# USB-C.net
KiCad netlist of a schematic drawn in Altium Designer
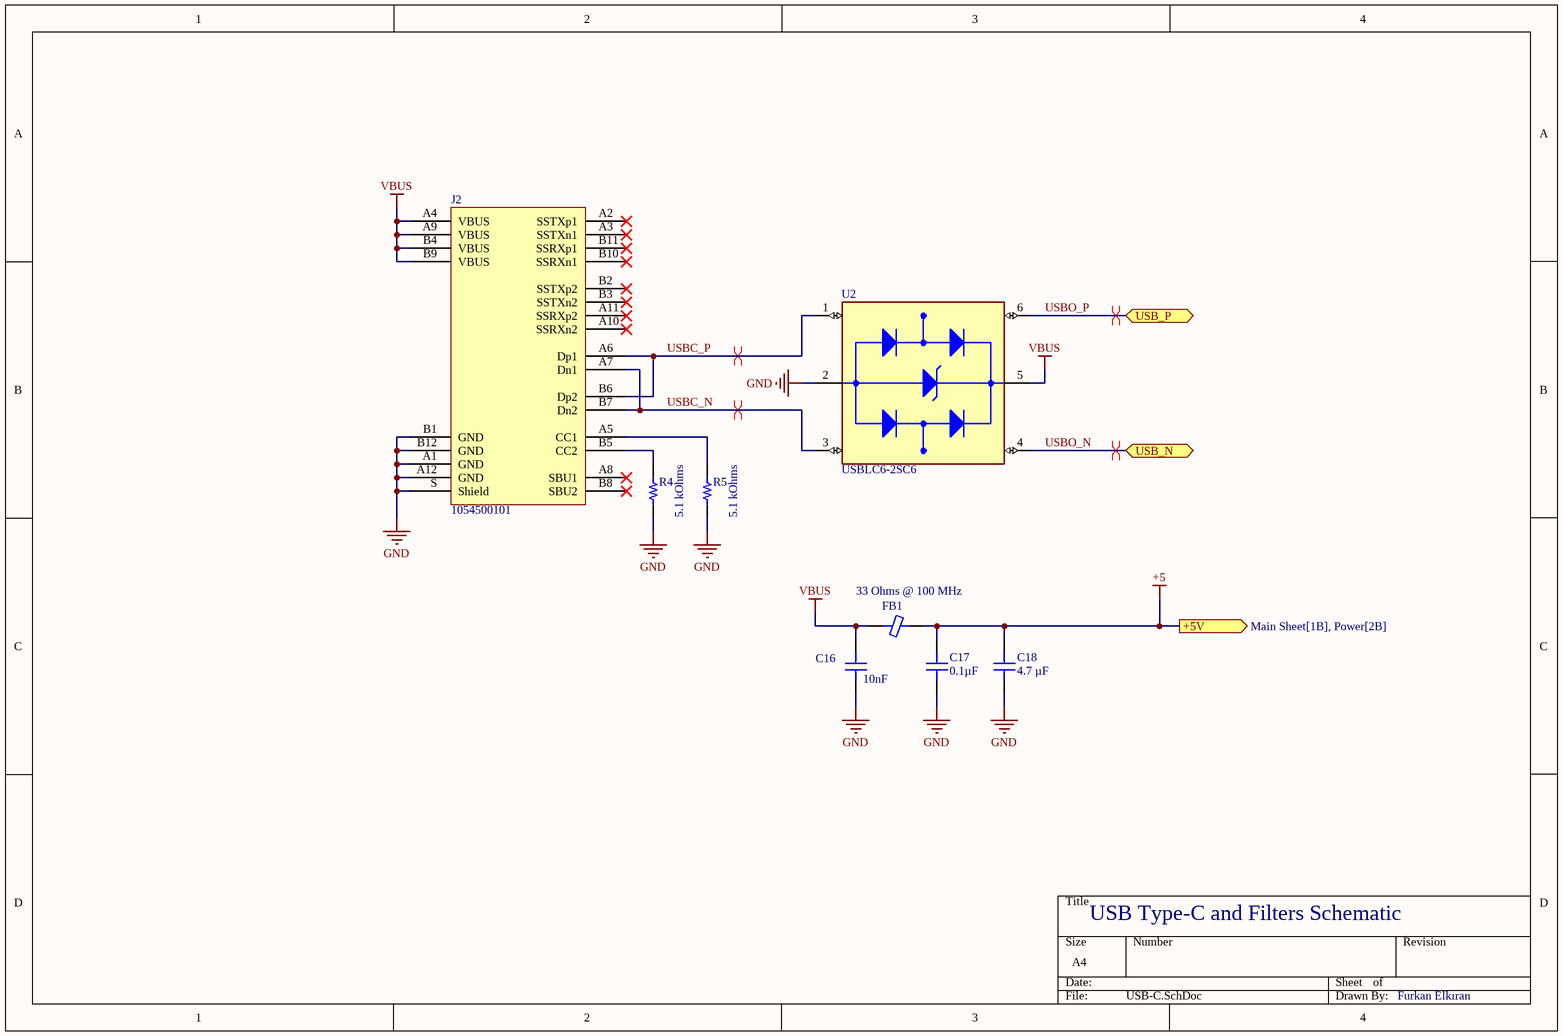
[diagram p0: USB-C.SchDoc]

(export (version "E")
  (design (tool "Eeschema 10.0.6"))
  (components
    (comp (ref "C16")
      (value "10000pF")
      (footprint "CAP 0402_1005")
      (description "CAP CER 10000PF 16V X7R 0402")
      (fields
        (field (name "PART NUMBER") "0402YC103JAT4A")
        (field (name "CAPACITANCE") "10nF")
        (field (name "MANUFACTURER") "AVX Corporation")
      )
      (libsource (lib "Celestial Altium Library - altium_library") (part "Capacitor"))
    )
    (comp (ref "C17")
      (value "0.1µF")
      (footprint "CAP 0402_1005")
      (description "CAP CER 0.1UF 16V X7R 0402")
      (fields
        (field (name "PART NUMBER") "0402YC104JAT4A")
        (field (name "CAPACITANCE") "0.1µF")
        (field (name "MANUFACTURER") "AVX Corporation")
      )
      (libsource (lib "Celestial Altium Library - altium_library") (part "Capacitor"))
    )
    (comp (ref "C18")
      (value "4.7 µF")
      (footprint "CAP 0805_2012")
      (description "CAP CER 4.7UF 16V X7R 0805")
      (fields
        (field (name "PART NUMBER") "C0805C475J4RACAUTO")
        (field (name "CAPACITANCE") "4.7 µF")
        (field (name "MANUFACTURER") "KEMET")
      )
      (libsource (lib "Celestial Altium Library - altium_library") (part "Capacitor"))
    )
    (comp (ref "FB1")
      (value "33 Ohms @ 100 MHz")
      (footprint "FER 0402_1005")
      (description "FBEAD 0402 33 OHM .40DC 300MA")
      (fields
        (field (name "PART NUMBER") "FB100505T-330Y-S")
        (field (name "MANUFACTURER") "Cal-Chip Electronics, Inc.")
      )
      (libsource (lib "Celestial Altium Library - altium_library") (part "Ferrite Chip"))
    )
    (comp (ref "J2")
      (value "1054500101")
      (footprint "Molex 1054500101")
      (description "CONN RCP USB3.1 TYPEC 24P SMD RA")
      (fields (field (name "MANUFACTURER") "Molex"))
      (libsource (lib "Celestial Altium Library - altium_library") (part "USB 3.0 Type C"))
    )
    (comp (ref "R4")
      (value "5.1 kOhms")
      (footprint "YAGEO RES 0402_1005")
      (description "RES SMD 5.1K OHM 5% 1/16W 0402")
      (fields (field (name "PART NUMBER") "AC0402JR-075K1L") (field (name "MANUFACTURER") "Yageo"))
      (libsource (lib "Celestial Altium Library - altium_library") (part "Resistor"))
    )
    (comp (ref "R5")
      (value "5.1 kOhms")
      (footprint "YAGEO RES 0402_1005")
      (description "RES SMD 5.1K OHM 5% 1/16W 0402")
      (fields (field (name "PART NUMBER") "AC0402JR-075K1L") (field (name "MANUFACTURER") "Yageo"))
      (libsource (lib "Celestial Altium Library - altium_library") (part "Resistor"))
    )
    (comp (ref "U2")
      (value "USBLC6-2SC6")
      (footprint "SOT95P280X145-6N")
      (description "17V Clamp 5A (8/20Âµs) Ipp Tvs Diode Surface Mount SOT-23-6")
      (fields (field (name "MF") "STMicroelectronics"))
      (libsource (lib "USBLC6-2SC6") (part "USBLC6-2SC6"))
    )
  )
  (nets
    (net (code "1") (name "+5") (class "Default")
      (node (ref "C17") (pin "2") (pinfunction "2_2") (pintype "passive"))
      (node (ref "C18") (pin "2") (pinfunction "2_2") (pintype "passive"))
      (node (ref "FB1") (pin "2") (pinfunction "2_2") (pintype "passive"))
    )
    (net (code "2") (name "/USBC_N") (class "Default")
      (node (ref "J2") (pin "A7") (pinfunction "Dn1_A7") (pintype "passive"))
      (node (ref "J2") (pin "B7") (pinfunction "Dn2_B7") (pintype "passive"))
      (node (ref "U2") (pin "3") (pinfunction "I/O2_IN_3") (pintype "bidirectional"))
    )
    (net (code "3") (name "/USBC_P") (class "Default")
      (node (ref "J2") (pin "A6") (pinfunction "Dp1_A6") (pintype "passive"))
      (node (ref "J2") (pin "B6") (pinfunction "Dp2_B6") (pintype "passive"))
      (node (ref "U2") (pin "1") (pinfunction "I/O1_IN_1") (pintype "bidirectional"))
    )
    (net (code "4") (name "/USBO_N") (class "Default")
      (node (ref "U2") (pin "4") (pinfunction "I/O2_OUT_4") (pintype "bidirectional"))
    )
    (net (code "5") (name "/USBO_P") (class "Default")
      (node (ref "U2") (pin "6") (pinfunction "I/O1_OUT_6") (pintype "bidirectional"))
    )
    (net (code "6") (name "GND") (class "Default")
      (node (ref "C16") (pin "1") (pinfunction "1_1") (pintype "passive"))
      (node (ref "C17") (pin "1") (pinfunction "1_1") (pintype "passive"))
      (node (ref "C18") (pin "1") (pinfunction "1_1") (pintype "passive"))
      (node (ref "J2") (pin "A1") (pinfunction "GND_A1") (pintype "passive"))
      (node (ref "J2") (pin "A12") (pinfunction "GND_A12") (pintype "passive"))
      (node (ref "J2") (pin "B1") (pinfunction "GND_B1") (pintype "passive"))
      (node (ref "J2") (pin "B12") (pinfunction "GND_B12") (pintype "passive"))
      (node (ref "J2") (pin "S") (pinfunction "Shield_S") (pintype "passive"))
      (node (ref "R4") (pin "1") (pinfunction "1_1") (pintype "passive"))
      (node (ref "R5") (pin "1") (pinfunction "1_1") (pintype "passive"))
      (node (ref "U2") (pin "2") (pinfunction "GND_2") (pintype "power_in"))
    )
    (net (code "7") (name "Net-(J2-CC1)") (class "Default")
      (node (ref "J2") (pin "A5") (pinfunction "CC1_A5") (pintype "passive"))
      (node (ref "R5") (pin "2") (pinfunction "2_2") (pintype "passive"))
    )
    (net (code "8") (name "Net-(J2-CC2)") (class "Default")
      (node (ref "J2") (pin "B5") (pinfunction "CC2_B5") (pintype "passive"))
      (node (ref "R4") (pin "2") (pinfunction "2_2") (pintype "passive"))
    )
    (net (code "9") (name "VBUS") (class "Default")
      (node (ref "C16") (pin "2") (pinfunction "2_2") (pintype "passive"))
      (node (ref "FB1") (pin "1") (pinfunction "1_1") (pintype "passive"))
      (node (ref "J2") (pin "A4") (pinfunction "VBUS_A4") (pintype "passive"))
      (node (ref "J2") (pin "A9") (pinfunction "VBUS_A9") (pintype "passive"))
      (node (ref "J2") (pin "B4") (pinfunction "VBUS_B4") (pintype "passive"))
      (node (ref "J2") (pin "B9") (pinfunction "VBUS_B9") (pintype "passive"))
      (node (ref "U2") (pin "5") (pinfunction "VBUS_5") (pintype "power_in"))
    )
    (net (code "10") (name "unconnected-(J2-SBU1-PadA8)") (class "Default")
      (node (ref "J2") (pin "A8") (pinfunction "SBU1_A8") (pintype "passive+no_connect"))
    )
    (net (code "11") (name "unconnected-(J2-SBU2-PadB8)") (class "Default")
      (node (ref "J2") (pin "B8") (pinfunction "SBU2_B8") (pintype "passive+no_connect"))
    )
    (net (code "12") (name "unconnected-(J2-SSRXn1-PadB10)") (class "Default")
      (node (ref "J2") (pin "B10") (pinfunction "SSRXn1_B10") (pintype "passive+no_connect"))
    )
    (net (code "13") (name "unconnected-(J2-SSRXn2-PadA10)") (class "Default")
      (node (ref "J2") (pin "A10") (pinfunction "SSRXn2_A10") (pintype "passive+no_connect"))
    )
    (net (code "14") (name "unconnected-(J2-SSRXp1-PadB11)") (class "Default")
      (node (ref "J2") (pin "B11") (pinfunction "SSRXp1_B11") (pintype "passive+no_connect"))
    )
    (net (code "15") (name "unconnected-(J2-SSRXp2-PadA11)") (class "Default")
      (node (ref "J2") (pin "A11") (pinfunction "SSRXp2_A11") (pintype "passive+no_connect"))
    )
    (net (code "16") (name "unconnected-(J2-SSTXn1-PadA3)") (class "Default")
      (node (ref "J2") (pin "A3") (pinfunction "SSTXn1_A3") (pintype "passive+no_connect"))
    )
    (net (code "17") (name "unconnected-(J2-SSTXn2-PadB3)") (class "Default")
      (node (ref "J2") (pin "B3") (pinfunction "SSTXn2_B3") (pintype "passive+no_connect"))
    )
    (net (code "18") (name "unconnected-(J2-SSTXp1-PadA2)") (class "Default")
      (node (ref "J2") (pin "A2") (pinfunction "SSTXp1_A2") (pintype "passive+no_connect"))
    )
    (net (code "19") (name "unconnected-(J2-SSTXp2-PadB2)") (class "Default")
      (node (ref "J2") (pin "B2") (pinfunction "SSTXp2_B2") (pintype "passive+no_connect"))
    )
  )
)
